# Sheet1.net
KiCad netlist of a schematic drawn in Altium Designer
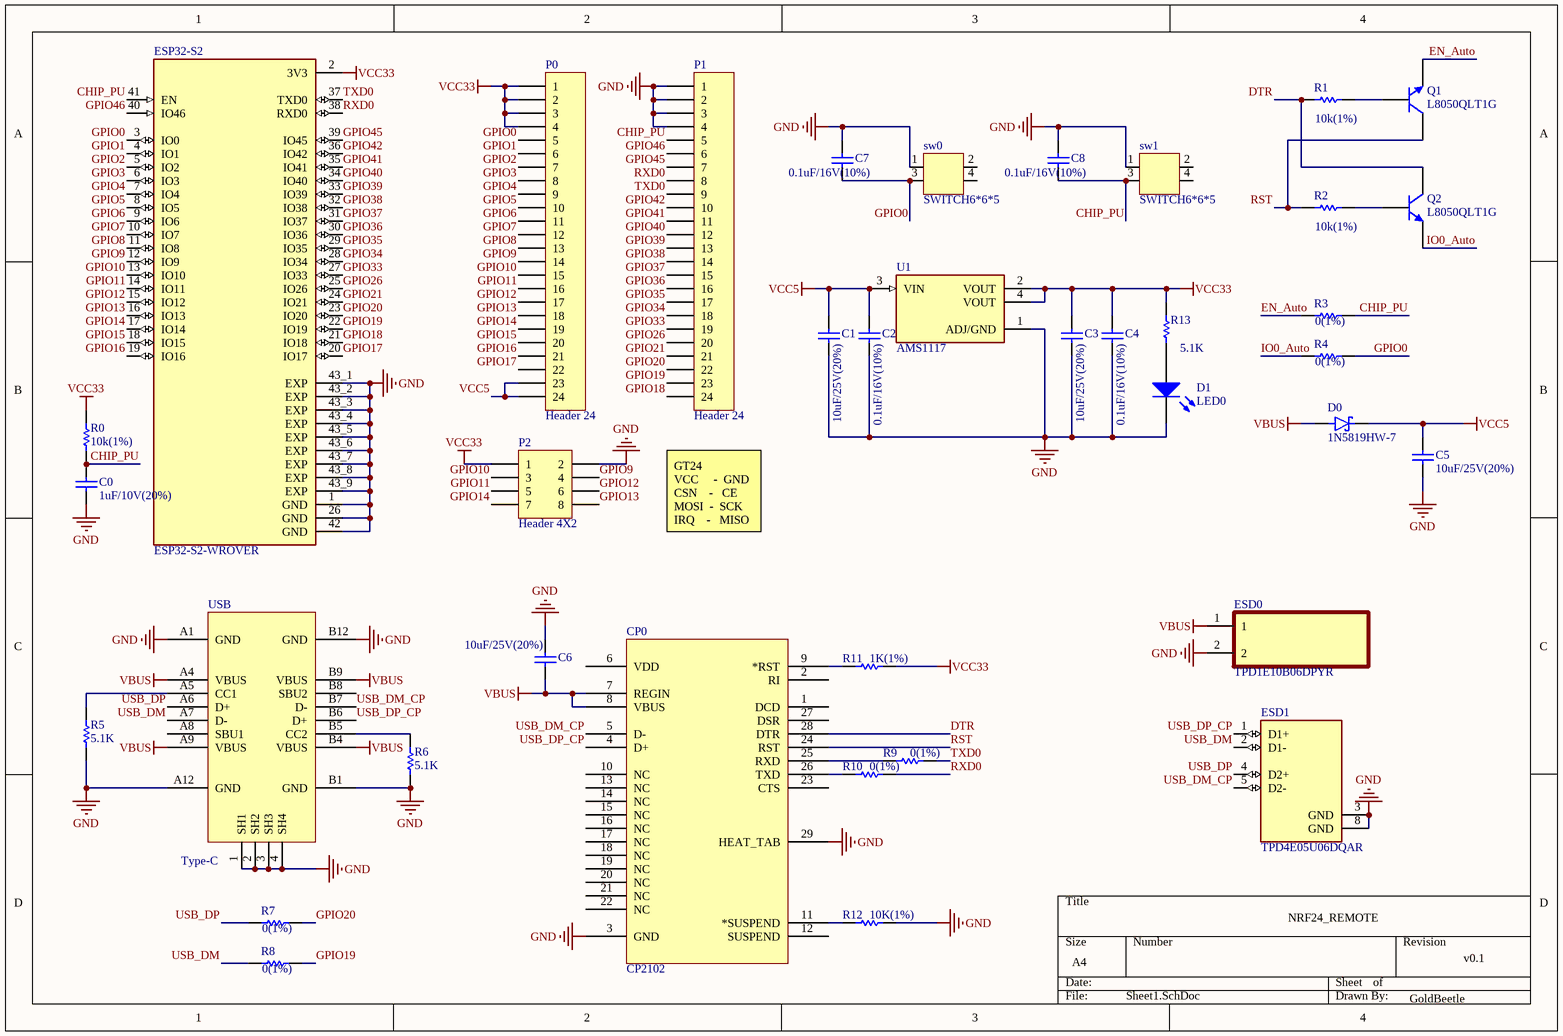
[diagram p0: Sheet1.SchDoc]

(export (version "E")
  (design (tool "Eeschema 10.0.6"))
  (components
    (comp (ref "C0")
      (value "1uF/10V(20%)")
      (footprint "C0805")
      (description "Capacitor")
      (fields (field (name "PUBLISHER") "Altium Limited"))
      (libsource (lib "Miscellaneous Devices") (part "Cap"))
    )
    (comp (ref "C1")
      (value "10uF/25V(20%)")
      (footprint "C0805")
      (description "Capacitor")
      (fields (field (name "PUBLISHER") "Altium Limited"))
      (libsource (lib "Miscellaneous Devices") (part "Cap"))
    )
    (comp (ref "C2")
      (value "0.1uF/16V(10%)")
      (footprint "C0805")
      (description "Capacitor")
      (fields (field (name "PUBLISHER") "Altium Limited"))
      (libsource (lib "Miscellaneous Devices") (part "Cap"))
    )
    (comp (ref "C3")
      (value "10uF/25V(20%)")
      (footprint "C0805")
      (description "Capacitor")
      (fields (field (name "PUBLISHER") "Altium Limited"))
      (libsource (lib "Miscellaneous Devices") (part "Cap"))
    )
    (comp (ref "C4")
      (value "0.1uF/16V(10%)")
      (footprint "C0805")
      (description "Capacitor")
      (fields (field (name "PUBLISHER") "Altium Limited"))
      (libsource (lib "Miscellaneous Devices") (part "Cap"))
    )
    (comp (ref "C5")
      (value "10uF/25V(20%)")
      (footprint "C0805")
      (description "Capacitor")
      (fields (field (name "PUBLISHER") "Altium Limited"))
      (libsource (lib "Miscellaneous Devices") (part "Cap"))
    )
    (comp (ref "C6")
      (value "10uF/25V(20%)")
      (footprint "C0805")
      (description "Capacitor")
      (fields (field (name "PUBLISHER") "Altium Limited"))
      (libsource (lib "Miscellaneous Devices") (part "Cap"))
    )
    (comp (ref "C7")
      (value "0.1uF/16V(10%)")
      (footprint "C0805")
      (description "Capacitor")
      (fields (field (name "PUBLISHER") "Altium Limited"))
      (libsource (lib "Miscellaneous Devices") (part "Cap"))
    )
    (comp (ref "C8")
      (value "0.1uF/16V(10%)")
      (footprint "C0805")
      (description "Capacitor")
      (fields (field (name "PUBLISHER") "Altium Limited"))
      (libsource (lib "Miscellaneous Devices") (part "Cap"))
    )
    (comp (ref "CP0")
      (value "CP2102")
      (footprint "QFN-28")
      (description "USB转TTL")
      (libsource (lib "Schlib1") (part "CP2102"))
    )
    (comp (ref "D0")
      (value "1N5819HW-7")
      (footprint "SOD3715X145N")
      (description "Diode Schottky 40 V 1A Surface Mount SOD-123")
      (fields (field (name "MF") "Diodes Inc."))
      (libsource (lib "Schlib1") (part "1N5819HW-7"))
    )
    (comp (ref "D1")
      (value "LED0")
      (footprint "C0805")
      (description "Typical INFRARED GaAs LED")
      (fields (field (name "PUBLISHER") "Altium Limited"))
      (libsource (lib "Miscellaneous Devices") (part "LED0"))
    )
    (comp (ref "ESD0")
      (value "TPD1E10B06DPYR")
      (footprint "DIO_TPD1E05U06DPYR(X1Son)")
      (description "Single-channel ESD in 0402 package with 10pF capacitance and 6-V breakdown 2-X1SON -40 to 125")
      (fields (field (name "MF") "Texas Instruments") (field (name "DIGI-KEY_PART_NUMBER") "296-30406-1-ND"))
      (libsource (lib "Schlib1") (part "TPD1E10B06DPYR"))
    )
    (comp (ref "ESD1")
      (value "TPD4E05U06DQAR")
      (footprint "TI_TPD4E05U06DQAR(USON10)")
      (description "14V Clamp 2.5A _8/20Âµs_ Ipp Tvs Diode Surface Mount 10-USON _2.5x1_")
      (fields (field (name "MF") "Texas Instruments"))
      (libsource (lib "Schlib1") (part "TPD4E05U06DQAR"))
    )
    (comp (ref "ESP32-S2")
      (value "ESP32-S2-WROVER")
      (footprint "MODULE_ESP32-S2-WROVER")
      (description "WiFi 802.11b/g/n Transceiver Module 2.4GHz PCB Trace Surface Mount")
      (fields (field (name "MF") "Espressif Systems"))
      (libsource (lib "Schlib1") (part "ESP32-S2-WROVER"))
    )
    (comp (ref "P0")
      (value "Header 24")
      (footprint "HDR1X24")
      (description "Header, 24-Pin")
      (fields (field (name "PUBLISHER") "Altium Limited"))
      (libsource (lib "Miscellaneous Connectors") (part "Header 24"))
    )
    (comp (ref "P1")
      (value "Header 24")
      (footprint "HDR1X24")
      (description "Header, 24-Pin")
      (fields (field (name "PUBLISHER") "Altium Limited"))
      (libsource (lib "Miscellaneous Connectors") (part "Header 24"))
    )
    (comp (ref "P2")
      (value "Header 4X2")
      (footprint "HDR2X4")
      (description "Header, 4-Pin, Dual row")
      (fields (field (name "PUBLISHER") "Altium Limited"))
      (libsource (lib "Miscellaneous Connectors") (part "Header 4X2"))
    )
    (comp (ref "Q1")
      (value "L8050QLT1G")
      (footprint "SOT100P237X110-3N")
      (description "NPN General Purpose Amplifier")
      (fields (field (name "PUBLISHER") "Altium Limited"))
      (libsource (lib "Miscellaneous Devices") (part "2N3904"))
    )
    (comp (ref "Q2")
      (value "L8050QLT1G")
      (footprint "SOT100P237X110-3N")
      (description "NPN General Purpose Amplifier")
      (fields (field (name "PUBLISHER") "Altium Limited"))
      (libsource (lib "Miscellaneous Devices") (part "2N3904"))
    )
    (comp (ref "R0")
      (value "10k(1%)")
      (footprint "C0805")
      (description "Resistor")
      (fields (field (name "PUBLISHER") "Altium Limited"))
      (libsource (lib "Miscellaneous Devices") (part "Res1"))
    )
    (comp (ref "R1")
      (value "10k(1%)")
      (footprint "C0805")
      (description "Resistor")
      (fields (field (name "PUBLISHER") "Altium Limited"))
      (libsource (lib "Miscellaneous Devices") (part "Res1"))
    )
    (comp (ref "R2")
      (value "10k(1%)")
      (footprint "C0805")
      (description "Resistor")
      (fields (field (name "PUBLISHER") "Altium Limited"))
      (libsource (lib "Miscellaneous Devices") (part "Res1"))
    )
    (comp (ref "R3")
      (value "0(1%)")
      (footprint "C0805")
      (description "Resistor")
      (fields (field (name "PUBLISHER") "Altium Limited"))
      (libsource (lib "Miscellaneous Devices") (part "Res1"))
    )
    (comp (ref "R4")
      (value "0(1%)")
      (footprint "C0805")
      (description "Resistor")
      (fields (field (name "PUBLISHER") "Altium Limited"))
      (libsource (lib "Miscellaneous Devices") (part "Res1"))
    )
    (comp (ref "R5")
      (value "5.1K")
      (footprint "C0805")
      (description "Resistor")
      (fields (field (name "PUBLISHER") "Altium Limited"))
      (libsource (lib "Miscellaneous Devices") (part "Res1"))
    )
    (comp (ref "R6")
      (value "5.1K")
      (footprint "C0805")
      (description "Resistor")
      (fields (field (name "PUBLISHER") "Altium Limited"))
      (libsource (lib "Miscellaneous Devices") (part "Res1"))
    )
    (comp (ref "R7")
      (value "0(1%)")
      (footprint "C0805")
      (description "Resistor")
      (fields (field (name "PUBLISHER") "Altium Limited"))
      (libsource (lib "Miscellaneous Devices") (part "Res1"))
    )
    (comp (ref "R8")
      (value "0(1%)")
      (footprint "C0805")
      (description "Resistor")
      (fields (field (name "PUBLISHER") "Altium Limited"))
      (libsource (lib "Miscellaneous Devices") (part "Res1"))
    )
    (comp (ref "R9")
      (value "0(1%)")
      (footprint "C0805")
      (description "Resistor")
      (fields (field (name "PUBLISHER") "Altium Limited"))
      (libsource (lib "Miscellaneous Devices") (part "Res1"))
    )
    (comp (ref "R10")
      (value "0(1%)")
      (footprint "C0805")
      (description "Resistor")
      (fields (field (name "PUBLISHER") "Altium Limited"))
      (libsource (lib "Miscellaneous Devices") (part "Res1"))
    )
    (comp (ref "R11")
      (value "1K(1%)")
      (footprint "C0805")
      (description "Resistor")
      (fields (field (name "PUBLISHER") "Altium Limited"))
      (libsource (lib "Miscellaneous Devices") (part "Res1"))
    )
    (comp (ref "R12")
      (value "10K(1%)")
      (footprint "C0805")
      (description "Resistor")
      (fields (field (name "PUBLISHER") "Altium Limited"))
      (libsource (lib "Miscellaneous Devices") (part "Res1"))
    )
    (comp (ref "R13")
      (value "5.1K")
      (footprint "C0805")
      (description "Resistor")
      (fields (field (name "PUBLISHER") "Altium Limited"))
      (libsource (lib "Miscellaneous Devices") (part "Res1"))
    )
    (comp (ref "sw0")
      (value "SWITCH6*6*5")
      (footprint "SWITCH6*6*5")
      (libsource (lib "Schlib1") (part "SWITCH6*6*5"))
    )
    (comp (ref "sw1")
      (value "SWITCH6*6*5")
      (footprint "SWITCH6*6*5")
      (libsource (lib "Schlib1") (part "SWITCH6*6*5"))
    )
    (comp (ref "U1")
      (value "AMS1117")
      (footprint "SOT229P700X180-4N")
      (description "UNO PLUS Arduino R3 Shield, Xbee Arduino IDE Wheeled Robotics Kit")
      (fields (field (name "MF") "Seeed Technology"))
      (libsource (lib "Schlib1") (part "AMS1117"))
    )
    (comp (ref "USB")
      (value "Type-C")
      (footprint "Type-C-TOP")
      (libsource (lib "Schlib1") (part "USB-Type-C-TOP"))
    )
  )
  (nets
    (net (code "1") (name "/CHIP_PU") (class "Default")
      (node (ref "C0") (pin "2") (pinfunction "2_2") (pintype "passive"))
      (node (ref "C8") (pin "2") (pinfunction "2_2") (pintype "passive"))
      (node (ref "ESP32-S2") (pin "41") (pinfunction "EN_41") (pintype "input"))
      (node (ref "P1") (pin "5") (pinfunction "5_5") (pintype "passive"))
      (node (ref "R0") (pin "1") (pinfunction "1_1") (pintype "passive"))
      (node (ref "R3") (pin "2") (pinfunction "2_2") (pintype "passive"))
      (node (ref "sw1") (pin "3") (pinfunction "3_3") (pintype "passive"))
    )
    (net (code "2") (name "/DTR") (class "Default")
      (node (ref "CP0") (pin "28") (pinfunction "DTR_28") (pintype "passive"))
      (node (ref "Q2") (pin "3") (pinfunction "C_3") (pintype "passive"))
      (node (ref "R1") (pin "1") (pinfunction "1_1") (pintype "passive"))
    )
    (net (code "3") (name "/EN_Auto") (class "Default")
      (node (ref "Q1") (pin "1") (pinfunction "E_1") (pintype "passive"))
      (node (ref "R3") (pin "1") (pinfunction "1_1") (pintype "passive"))
    )
    (net (code "4") (name "/GPIO0") (class "Default")
      (node (ref "C7") (pin "2") (pinfunction "2_2") (pintype "passive"))
      (node (ref "ESP32-S2") (pin "3") (pinfunction "IO0_3") (pintype "bidirectional"))
      (node (ref "P0") (pin "5") (pinfunction "5_5") (pintype "passive"))
      (node (ref "R4") (pin "2") (pinfunction "2_2") (pintype "passive"))
      (node (ref "sw0") (pin "3") (pinfunction "3_3") (pintype "passive"))
    )
    (net (code "5") (name "/GPIO1") (class "Default")
      (node (ref "ESP32-S2") (pin "4") (pinfunction "IO1_4") (pintype "bidirectional"))
      (node (ref "P0") (pin "6") (pinfunction "6_6") (pintype "passive"))
    )
    (net (code "6") (name "/GPIO2") (class "Default")
      (node (ref "ESP32-S2") (pin "5") (pinfunction "IO2_5") (pintype "bidirectional"))
      (node (ref "P0") (pin "7") (pinfunction "7_7") (pintype "passive"))
    )
    (net (code "7") (name "/GPIO3") (class "Default")
      (node (ref "ESP32-S2") (pin "6") (pinfunction "IO3_6") (pintype "bidirectional"))
      (node (ref "P0") (pin "8") (pinfunction "8_8") (pintype "passive"))
    )
    (net (code "8") (name "/GPIO4") (class "Default")
      (node (ref "ESP32-S2") (pin "7") (pinfunction "IO4_7") (pintype "bidirectional"))
      (node (ref "P0") (pin "9") (pinfunction "9_9") (pintype "passive"))
    )
    (net (code "9") (name "/GPIO5") (class "Default")
      (node (ref "ESP32-S2") (pin "8") (pinfunction "IO5_8") (pintype "bidirectional"))
      (node (ref "P0") (pin "10") (pinfunction "10_10") (pintype "passive"))
    )
    (net (code "10") (name "/GPIO6") (class "Default")
      (node (ref "ESP32-S2") (pin "9") (pinfunction "IO6_9") (pintype "bidirectional"))
      (node (ref "P0") (pin "11") (pinfunction "11_11") (pintype "passive"))
    )
    (net (code "11") (name "/GPIO7") (class "Default")
      (node (ref "ESP32-S2") (pin "10") (pinfunction "IO7_10") (pintype "bidirectional"))
      (node (ref "P0") (pin "12") (pinfunction "12_12") (pintype "passive"))
    )
    (net (code "12") (name "/GPIO8") (class "Default")
      (node (ref "ESP32-S2") (pin "11") (pinfunction "IO8_11") (pintype "bidirectional"))
      (node (ref "P0") (pin "13") (pinfunction "13_13") (pintype "passive"))
    )
    (net (code "13") (name "/GPIO9") (class "Default")
      (node (ref "ESP32-S2") (pin "12") (pinfunction "IO9_12") (pintype "bidirectional"))
      (node (ref "P0") (pin "14") (pinfunction "14_14") (pintype "passive"))
      (node (ref "P2") (pin "4") (pinfunction "4_4") (pintype "passive"))
    )
    (net (code "14") (name "/GPIO10") (class "Default")
      (node (ref "ESP32-S2") (pin "13") (pinfunction "IO10_13") (pintype "bidirectional"))
      (node (ref "P0") (pin "15") (pinfunction "15_15") (pintype "passive"))
      (node (ref "P2") (pin "3") (pinfunction "3_3") (pintype "passive"))
    )
    (net (code "15") (name "/GPIO11") (class "Default")
      (node (ref "ESP32-S2") (pin "14") (pinfunction "IO11_14") (pintype "bidirectional"))
      (node (ref "P0") (pin "16") (pinfunction "16_16") (pintype "passive"))
      (node (ref "P2") (pin "5") (pinfunction "5_5") (pintype "passive"))
    )
    (net (code "16") (name "/GPIO12") (class "Default")
      (node (ref "ESP32-S2") (pin "15") (pinfunction "IO12_15") (pintype "bidirectional"))
      (node (ref "P0") (pin "17") (pinfunction "17_17") (pintype "passive"))
      (node (ref "P2") (pin "6") (pinfunction "6_6") (pintype "passive"))
    )
    (net (code "17") (name "/GPIO13") (class "Default")
      (node (ref "ESP32-S2") (pin "16") (pinfunction "IO13_16") (pintype "bidirectional"))
      (node (ref "P0") (pin "18") (pinfunction "18_18") (pintype "passive"))
      (node (ref "P2") (pin "8") (pinfunction "8_8") (pintype "passive"))
    )
    (net (code "18") (name "/GPIO14") (class "Default")
      (node (ref "ESP32-S2") (pin "17") (pinfunction "IO14_17") (pintype "bidirectional"))
      (node (ref "P0") (pin "19") (pinfunction "19_19") (pintype "passive"))
      (node (ref "P2") (pin "7") (pinfunction "7_7") (pintype "passive"))
    )
    (net (code "19") (name "/GPIO15") (class "Default")
      (node (ref "ESP32-S2") (pin "18") (pinfunction "IO15_18") (pintype "bidirectional"))
      (node (ref "P0") (pin "20") (pinfunction "20_20") (pintype "passive"))
    )
    (net (code "20") (name "/GPIO16") (class "Default")
      (node (ref "ESP32-S2") (pin "19") (pinfunction "IO16_19") (pintype "bidirectional"))
      (node (ref "P0") (pin "21") (pinfunction "21_21") (pintype "passive"))
    )
    (net (code "21") (name "/GPIO17") (class "Default")
      (node (ref "ESP32-S2") (pin "20") (pinfunction "IO17_20") (pintype "bidirectional"))
      (node (ref "P0") (pin "22") (pinfunction "22_22") (pintype "passive"))
    )
    (net (code "22") (name "/GPIO18") (class "Default")
      (node (ref "ESP32-S2") (pin "21") (pinfunction "IO18_21") (pintype "bidirectional"))
      (node (ref "P1") (pin "24") (pinfunction "24_24") (pintype "passive"))
    )
    (net (code "23") (name "/GPIO19") (class "Default")
      (node (ref "ESP32-S2") (pin "22") (pinfunction "IO19_22") (pintype "bidirectional"))
      (node (ref "P1") (pin "23") (pinfunction "23_23") (pintype "passive"))
      (node (ref "R8") (pin "2") (pinfunction "2_2") (pintype "passive"))
    )
    (net (code "24") (name "/GPIO20") (class "Default")
      (node (ref "ESP32-S2") (pin "23") (pinfunction "IO20_23") (pintype "bidirectional"))
      (node (ref "P1") (pin "22") (pinfunction "22_22") (pintype "passive"))
      (node (ref "R7") (pin "2") (pinfunction "2_2") (pintype "passive"))
    )
    (net (code "25") (name "/GPIO21") (class "Default")
      (node (ref "ESP32-S2") (pin "24") (pinfunction "IO21_24") (pintype "bidirectional"))
      (node (ref "P1") (pin "21") (pinfunction "21_21") (pintype "passive"))
    )
    (net (code "26") (name "/GPIO26") (class "Default")
      (node (ref "ESP32-S2") (pin "25") (pinfunction "IO26_25") (pintype "bidirectional"))
      (node (ref "P1") (pin "20") (pinfunction "20_20") (pintype "passive"))
    )
    (net (code "27") (name "/GPIO33") (class "Default")
      (node (ref "ESP32-S2") (pin "27") (pinfunction "IO33_27") (pintype "bidirectional"))
      (node (ref "P1") (pin "19") (pinfunction "19_19") (pintype "passive"))
    )
    (net (code "28") (name "/GPIO34") (class "Default")
      (node (ref "ESP32-S2") (pin "28") (pinfunction "IO34_28") (pintype "bidirectional"))
      (node (ref "P1") (pin "18") (pinfunction "18_18") (pintype "passive"))
    )
    (net (code "29") (name "/GPIO35") (class "Default")
      (node (ref "ESP32-S2") (pin "29") (pinfunction "IO35_29") (pintype "bidirectional"))
      (node (ref "P1") (pin "17") (pinfunction "17_17") (pintype "passive"))
    )
    (net (code "30") (name "/GPIO36") (class "Default")
      (node (ref "ESP32-S2") (pin "30") (pinfunction "IO36_30") (pintype "bidirectional"))
      (node (ref "P1") (pin "16") (pinfunction "16_16") (pintype "passive"))
    )
    (net (code "31") (name "/GPIO37") (class "Default")
      (node (ref "ESP32-S2") (pin "31") (pinfunction "IO37_31") (pintype "bidirectional"))
      (node (ref "P1") (pin "15") (pinfunction "15_15") (pintype "passive"))
    )
    (net (code "32") (name "/GPIO38") (class "Default")
      (node (ref "ESP32-S2") (pin "32") (pinfunction "IO38_32") (pintype "bidirectional"))
      (node (ref "P1") (pin "14") (pinfunction "14_14") (pintype "passive"))
    )
    (net (code "33") (name "/GPIO39") (class "Default")
      (node (ref "ESP32-S2") (pin "33") (pinfunction "IO39_33") (pintype "bidirectional"))
      (node (ref "P1") (pin "13") (pinfunction "13_13") (pintype "passive"))
    )
    (net (code "34") (name "/GPIO40") (class "Default")
      (node (ref "ESP32-S2") (pin "34") (pinfunction "IO40_34") (pintype "bidirectional"))
      (node (ref "P1") (pin "12") (pinfunction "12_12") (pintype "passive"))
    )
    (net (code "35") (name "/GPIO41") (class "Default")
      (node (ref "ESP32-S2") (pin "35") (pinfunction "IO41_35") (pintype "bidirectional"))
      (node (ref "P1") (pin "11") (pinfunction "11_11") (pintype "passive"))
    )
    (net (code "36") (name "/GPIO42") (class "Default")
      (node (ref "ESP32-S2") (pin "36") (pinfunction "IO42_36") (pintype "bidirectional"))
      (node (ref "P1") (pin "10") (pinfunction "10_10") (pintype "passive"))
    )
    (net (code "37") (name "/GPIO45") (class "Default")
      (node (ref "ESP32-S2") (pin "39") (pinfunction "IO45_39") (pintype "bidirectional"))
      (node (ref "P1") (pin "7") (pinfunction "7_7") (pintype "passive"))
    )
    (net (code "38") (name "/GPIO46") (class "Default")
      (node (ref "ESP32-S2") (pin "40") (pinfunction "IO46_40") (pintype "input"))
      (node (ref "P1") (pin "6") (pinfunction "6_6") (pintype "passive"))
    )
    (net (code "39") (name "/IO0_Auto") (class "Default")
      (node (ref "Q2") (pin "1") (pinfunction "E_1") (pintype "passive"))
      (node (ref "R4") (pin "1") (pinfunction "1_1") (pintype "passive"))
    )
    (net (code "40") (name "/RST") (class "Default")
      (node (ref "CP0") (pin "24") (pinfunction "RST_24") (pintype "passive"))
      (node (ref "Q1") (pin "3") (pinfunction "C_3") (pintype "passive"))
      (node (ref "R2") (pin "1") (pinfunction "1_1") (pintype "passive"))
    )
    (net (code "41") (name "/RXD0") (class "Default")
      (node (ref "ESP32-S2") (pin "38") (pinfunction "RXD0_38") (pintype "bidirectional"))
      (node (ref "P1") (pin "8") (pinfunction "8_8") (pintype "passive"))
      (node (ref "R10") (pin "2") (pinfunction "2_2") (pintype "passive"))
    )
    (net (code "42") (name "/TXD0") (class "Default")
      (node (ref "ESP32-S2") (pin "37") (pinfunction "TXD0_37") (pintype "bidirectional"))
      (node (ref "P1") (pin "9") (pinfunction "9_9") (pintype "passive"))
      (node (ref "R9") (pin "2") (pinfunction "2_2") (pintype "passive"))
    )
    (net (code "43") (name "/USB_DM") (class "Default")
      (node (ref "ESD1") (pin "2") (pinfunction "D1-_2") (pintype "bidirectional"))
      (node (ref "R8") (pin "1") (pinfunction "1_1") (pintype "passive"))
      (node (ref "USB") (pin "A7") (pinfunction "D-_A7") (pintype "passive"))
    )
    (net (code "44") (name "/USB_DM_CP") (class "Default")
      (node (ref "CP0") (pin "5") (pinfunction "D-_5") (pintype "passive"))
      (node (ref "ESD1") (pin "5") (pinfunction "D2-_5") (pintype "bidirectional"))
      (node (ref "USB") (pin "B7") (pinfunction "D-_B7") (pintype "passive"))
    )
    (net (code "45") (name "/USB_DP") (class "Default")
      (node (ref "ESD1") (pin "4") (pinfunction "D2+_4") (pintype "bidirectional"))
      (node (ref "R7") (pin "1") (pinfunction "1_1") (pintype "passive"))
      (node (ref "USB") (pin "A6") (pinfunction "D+_A6") (pintype "passive"))
    )
    (net (code "46") (name "/USB_DP_CP") (class "Default")
      (node (ref "CP0") (pin "4") (pinfunction "D+_4") (pintype "passive"))
      (node (ref "ESD1") (pin "1") (pinfunction "D1+_1") (pintype "bidirectional"))
      (node (ref "USB") (pin "B6") (pinfunction "D+_B6") (pintype "passive"))
    )
    (net (code "47") (name "GND") (class "Default")
      (node (ref "C0") (pin "1") (pinfunction "1_1") (pintype "passive"))
      (node (ref "C1") (pin "1") (pinfunction "1_1") (pintype "passive"))
      (node (ref "C2") (pin "1") (pinfunction "1_1") (pintype "passive"))
      (node (ref "C3") (pin "1") (pinfunction "1_1") (pintype "passive"))
      (node (ref "C4") (pin "1") (pinfunction "1_1") (pintype "passive"))
      (node (ref "C5") (pin "1") (pinfunction "1_1") (pintype "passive"))
      (node (ref "C6") (pin "1") (pinfunction "1_1") (pintype "passive"))
      (node (ref "C7") (pin "1") (pinfunction "1_1") (pintype "passive"))
      (node (ref "C8") (pin "1") (pinfunction "1_1") (pintype "passive"))
      (node (ref "CP0") (pin "29") (pinfunction "HEAT_TAB_29") (pintype "passive"))
      (node (ref "CP0") (pin "3") (pinfunction "GND_3") (pintype "passive"))
      (node (ref "D1") (pin "2") (pinfunction "K_2") (pintype "passive"))
      (node (ref "ESD0") (pin "2") (pinfunction "2_2") (pintype "passive"))
      (node (ref "ESD1") (pin "3") (pinfunction "GND_3") (pintype "passive"))
      (node (ref "ESD1") (pin "8") (pinfunction "GND_8") (pintype "passive"))
      (node (ref "ESP32-S2") (pin "1") (pinfunction "GND_1") (pintype "passive"))
      (node (ref "ESP32-S2") (pin "26") (pinfunction "GND_26") (pintype "passive"))
      (node (ref "ESP32-S2") (pin "42") (pinfunction "GND_42") (pintype "passive"))
      (node (ref "ESP32-S2") (pin "43_1") (pinfunction "EXP_43_1") (pintype "passive"))
      (node (ref "ESP32-S2") (pin "43_2") (pinfunction "EXP_43_2") (pintype "passive"))
      (node (ref "ESP32-S2") (pin "43_3") (pinfunction "EXP_43_3") (pintype "passive"))
      (node (ref "ESP32-S2") (pin "43_4") (pinfunction "EXP_43_4") (pintype "passive"))
      (node (ref "ESP32-S2") (pin "43_5") (pinfunction "EXP_43_5") (pintype "passive"))
      (node (ref "ESP32-S2") (pin "43_6") (pinfunction "EXP_43_6") (pintype "passive"))
      (node (ref "ESP32-S2") (pin "43_7") (pinfunction "EXP_43_7") (pintype "passive"))
      (node (ref "ESP32-S2") (pin "43_8") (pinfunction "EXP_43_8") (pintype "passive"))
      (node (ref "ESP32-S2") (pin "43_9") (pinfunction "EXP_43_9") (pintype "passive"))
      (node (ref "P1") (pin "1") (pinfunction "1_1") (pintype "passive"))
      (node (ref "P1") (pin "2") (pinfunction "2_2") (pintype "passive"))
      (node (ref "P1") (pin "3") (pinfunction "3_3") (pintype "passive"))
      (node (ref "P1") (pin "4") (pinfunction "4_4") (pintype "passive"))
      (node (ref "P2") (pin "2") (pinfunction "2_2") (pintype "passive"))
      (node (ref "R12") (pin "2") (pinfunction "2_2") (pintype "passive"))
      (node (ref "R5") (pin "1") (pinfunction "1_1") (pintype "passive"))
      (node (ref "R6") (pin "1") (pinfunction "1_1") (pintype "passive"))
      (node (ref "U1") (pin "1") (pinfunction "ADJ/GND_1") (pintype "passive"))
      (node (ref "USB") (pin "1") (pinfunction "SH1_1") (pintype "passive"))
      (node (ref "USB") (pin "2") (pinfunction "SH2_2") (pintype "passive"))
      (node (ref "USB") (pin "3") (pinfunction "SH3_3") (pintype "passive"))
      (node (ref "USB") (pin "4") (pinfunction "SH4_4") (pintype "passive"))
      (node (ref "USB") (pin "A1") (pinfunction "GND_A1") (pintype "passive"))
      (node (ref "USB") (pin "A12") (pinfunction "GND_A12") (pintype "passive"))
      (node (ref "USB") (pin "B1") (pinfunction "GND_B1") (pintype "passive"))
      (node (ref "USB") (pin "B12") (pinfunction "GND_B12") (pintype "passive"))
      (node (ref "sw0") (pin "1") (pinfunction "1_1") (pintype "passive"))
      (node (ref "sw1") (pin "1") (pinfunction "1_1") (pintype "passive"))
    )
    (net (code "48") (name "Net-(CP0-*RST)") (class "Default")
      (node (ref "CP0") (pin "9") (pinfunction "*RST_9") (pintype "passive"))
      (node (ref "R11") (pin "1") (pinfunction "1_1") (pintype "passive"))
    )
    (net (code "49") (name "Net-(CP0-*SUSPEND)") (class "Default")
      (node (ref "CP0") (pin "11") (pinfunction "*SUSPEND_11") (pintype "passive"))
      (node (ref "R12") (pin "1") (pinfunction "1_1") (pintype "passive"))
    )
    (net (code "50") (name "Net-(CP0-RXD)") (class "Default")
      (node (ref "CP0") (pin "25") (pinfunction "RXD_25") (pintype "passive"))
      (node (ref "R9") (pin "1") (pinfunction "1_1") (pintype "passive"))
    )
    (net (code "51") (name "Net-(CP0-TXD)") (class "Default")
      (node (ref "CP0") (pin "26") (pinfunction "TXD_26") (pintype "passive"))
      (node (ref "R10") (pin "1") (pinfunction "1_1") (pintype "passive"))
    )
    (net (code "52") (name "Net-(D1-A)") (class "Default")
      (node (ref "D1") (pin "1") (pinfunction "A_1") (pintype "passive"))
      (node (ref "R13") (pin "2") (pinfunction "2_2") (pintype "passive"))
    )
    (net (code "53") (name "Net-(Q1-B)") (class "Default")
      (node (ref "Q1") (pin "2") (pinfunction "B_2") (pintype "passive"))
      (node (ref "R1") (pin "2") (pinfunction "2_2") (pintype "passive"))
    )
    (net (code "54") (name "Net-(Q2-B)") (class "Default")
      (node (ref "Q2") (pin "2") (pinfunction "B_2") (pintype "passive"))
      (node (ref "R2") (pin "2") (pinfunction "2_2") (pintype "passive"))
    )
    (net (code "55") (name "Net-(USB-CC1)") (class "Default")
      (node (ref "R5") (pin "2") (pinfunction "2_2") (pintype "passive"))
      (node (ref "USB") (pin "A5") (pinfunction "CC1_A5") (pintype "passive"))
    )
    (net (code "56") (name "Net-(USB-CC2)") (class "Default")
      (node (ref "R6") (pin "2") (pinfunction "2_2") (pintype "passive"))
      (node (ref "USB") (pin "B5") (pinfunction "CC2_B5") (pintype "passive"))
    )
    (net (code "57") (name "VBUS") (class "Default")
      (node (ref "C6") (pin "2") (pinfunction "2_2") (pintype "passive"))
      (node (ref "CP0") (pin "7") (pinfunction "REGIN_7") (pintype "passive"))
      (node (ref "CP0") (pin "8") (pinfunction "VBUS_8") (pintype "passive"))
      (node (ref "D0") (pin "A") (pinfunction "A_A") (pintype "passive"))
      (node (ref "ESD0") (pin "1") (pinfunction "1_1") (pintype "passive"))
      (node (ref "USB") (pin "A4") (pinfunction "VBUS_A4") (pintype "passive"))
      (node (ref "USB") (pin "A9") (pinfunction "VBUS_A9") (pintype "passive"))
      (node (ref "USB") (pin "B4") (pinfunction "VBUS_B4") (pintype "passive"))
      (node (ref "USB") (pin "B9") (pinfunction "VBUS_B9") (pintype "passive"))
    )
    (net (code "58") (name "VCC5") (class "Default")
      (node (ref "C1") (pin "2") (pinfunction "2_2") (pintype "passive"))
      (node (ref "C2") (pin "2") (pinfunction "2_2") (pintype "passive"))
      (node (ref "C5") (pin "2") (pinfunction "2_2") (pintype "passive"))
      (node (ref "D0") (pin "C") (pinfunction "K_C") (pintype "passive"))
      (node (ref "P0") (pin "23") (pinfunction "23_23") (pintype "passive"))
      (node (ref "P0") (pin "24") (pinfunction "24_24") (pintype "passive"))
      (node (ref "U1") (pin "3") (pinfunction "VIN_3") (pintype "input"))
    )
    (net (code "59") (name "VCC33") (class "Default")
      (node (ref "C3") (pin "2") (pinfunction "2_2") (pintype "passive"))
      (node (ref "C4") (pin "2") (pinfunction "2_2") (pintype "passive"))
      (node (ref "ESP32-S2") (pin "2") (pinfunction "3V3_2") (pintype "power_in"))
      (node (ref "P0") (pin "1") (pinfunction "1_1") (pintype "passive"))
      (node (ref "P0") (pin "2") (pinfunction "2_2") (pintype "passive"))
      (node (ref "P0") (pin "3") (pinfunction "3_3") (pintype "passive"))
      (node (ref "P0") (pin "4") (pinfunction "4_4") (pintype "passive"))
      (node (ref "P2") (pin "1") (pinfunction "1_1") (pintype "passive"))
      (node (ref "R0") (pin "2") (pinfunction "2_2") (pintype "passive"))
      (node (ref "R11") (pin "2") (pinfunction "2_2") (pintype "passive"))
      (node (ref "R13") (pin "1") (pinfunction "1_1") (pintype "passive"))
      (node (ref "U1") (pin "2") (pinfunction "VOUT_2") (pintype "passive"))
      (node (ref "U1") (pin "4") (pinfunction "VOUT_4") (pintype "passive"))
    )
    (net (code "60") (name "unconnected-(CP0-CTS-Pad23)") (class "Default")
      (node (ref "CP0") (pin "23") (pinfunction "CTS_23") (pintype "passive"))
    )
    (net (code "61") (name "unconnected-(CP0-DCD-Pad1)") (class "Default")
      (node (ref "CP0") (pin "1") (pinfunction "DCD_1") (pintype "passive"))
    )
    (net (code "62") (name "unconnected-(CP0-DSR-Pad27)") (class "Default")
      (node (ref "CP0") (pin "27") (pinfunction "DSR_27") (pintype "passive"))
    )
    (net (code "63") (name "unconnected-(CP0-NC-Pad10)") (class "Default")
      (node (ref "CP0") (pin "10") (pinfunction "NC_10") (pintype "passive"))
    )
    (net (code "64") (name "unconnected-(CP0-NC-Pad13)") (class "Default")
      (node (ref "CP0") (pin "13") (pinfunction "NC_13") (pintype "passive"))
    )
    (net (code "65") (name "unconnected-(CP0-NC-Pad14)") (class "Default")
      (node (ref "CP0") (pin "14") (pinfunction "NC_14") (pintype "passive"))
    )
    (net (code "66") (name "unconnected-(CP0-NC-Pad15)") (class "Default")
      (node (ref "CP0") (pin "15") (pinfunction "NC_15") (pintype "passive"))
    )
    (net (code "67") (name "unconnected-(CP0-NC-Pad16)") (class "Default")
      (node (ref "CP0") (pin "16") (pinfunction "NC_16") (pintype "passive"))
    )
    (net (code "68") (name "unconnected-(CP0-NC-Pad17)") (class "Default")
      (node (ref "CP0") (pin "17") (pinfunction "NC_17") (pintype "passive"))
    )
    (net (code "69") (name "unconnected-(CP0-NC-Pad18)") (class "Default")
      (node (ref "CP0") (pin "18") (pinfunction "NC_18") (pintype "passive"))
    )
    (net (code "70") (name "unconnected-(CP0-NC-Pad19)") (class "Default")
      (node (ref "CP0") (pin "19") (pinfunction "NC_19") (pintype "passive"))
    )
    (net (code "71") (name "unconnected-(CP0-NC-Pad20)") (class "Default")
      (node (ref "CP0") (pin "20") (pinfunction "NC_20") (pintype "passive"))
    )
    (net (code "72") (name "unconnected-(CP0-NC-Pad21)") (class "Default")
      (node (ref "CP0") (pin "21") (pinfunction "NC_21") (pintype "passive"))
    )
    (net (code "73") (name "unconnected-(CP0-NC-Pad22)") (class "Default")
      (node (ref "CP0") (pin "22") (pinfunction "NC_22") (pintype "passive"))
    )
    (net (code "74") (name "unconnected-(CP0-RI-Pad2)") (class "Default")
      (node (ref "CP0") (pin "2") (pinfunction "RI_2") (pintype "passive"))
    )
    (net (code "75") (name "unconnected-(CP0-SUSPEND-Pad12)") (class "Default")
      (node (ref "CP0") (pin "12") (pinfunction "SUSPEND_12") (pintype "passive"))
    )
    (net (code "76") (name "unconnected-(CP0-VDD-Pad6)") (class "Default")
      (node (ref "CP0") (pin "6") (pinfunction "VDD_6") (pintype "passive"))
    )
    (net (code "77") (name "unconnected-(USB-SBU1-PadA8)") (class "Default")
      (node (ref "USB") (pin "A8") (pinfunction "SBU1_A8") (pintype "passive"))
    )
    (net (code "78") (name "unconnected-(USB-SBU2-PadB8)") (class "Default")
      (node (ref "USB") (pin "B8") (pinfunction "SBU2_B8") (pintype "passive"))
    )
    (net (code "79") (name "unconnected-(sw0-Pad2)") (class "Default")
      (node (ref "sw0") (pin "2") (pinfunction "2_2") (pintype "passive"))
    )
    (net (code "80") (name "unconnected-(sw0-Pad4)") (class "Default")
      (node (ref "sw0") (pin "4") (pinfunction "4_4") (pintype "passive"))
    )
    (net (code "81") (name "unconnected-(sw1-Pad2)") (class "Default")
      (node (ref "sw1") (pin "2") (pinfunction "2_2") (pintype "passive"))
    )
    (net (code "82") (name "unconnected-(sw1-Pad4)") (class "Default")
      (node (ref "sw1") (pin "4") (pinfunction "4_4") (pintype "passive"))
    )
  )
)
